# rpi_ad7705.net
KiCad netlist of a schematic drawn in EAGLE
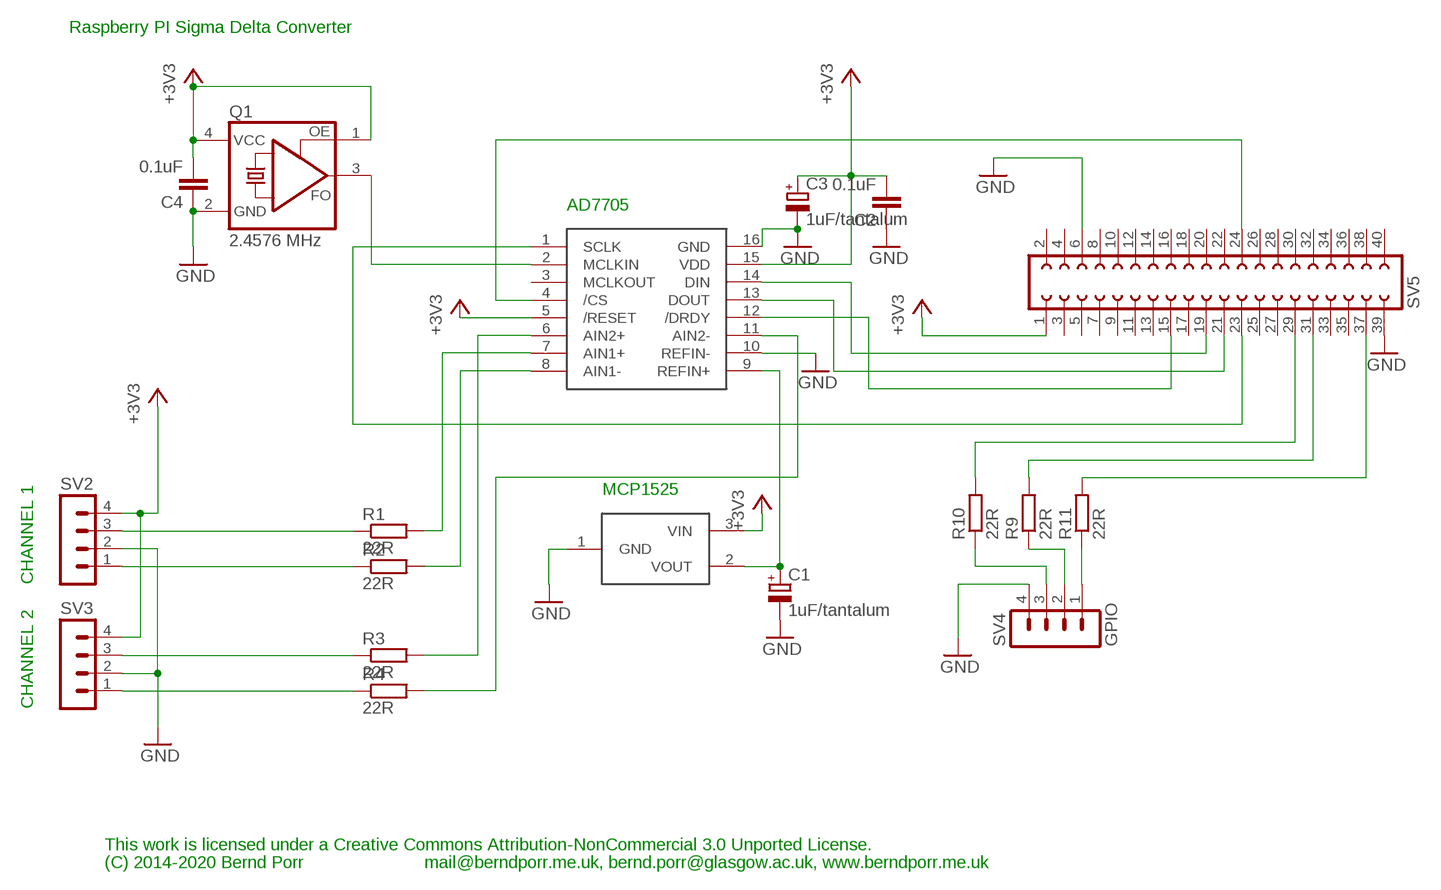
[diagram p0: schematic, sheet 1]

(export (version "E")
  (design (tool "Eeschema 10.0.6"))
  (components
    (comp (ref "C1")
      (value "1uF/tantalum")
      (footprint "eagle-import:TT2D7")
      (libsource (lib "eagle-import") (part "CPOL-EUTT2D7"))
    )
    (comp (ref "C2")
      (value "0.1uF")
      (footprint "eagle-import:C5B2.5")
      (libsource (lib "eagle-import") (part "C5/2.5"))
    )
    (comp (ref "C3")
      (value "1uF/tantalum")
      (footprint "eagle-import:TT2D7")
      (libsource (lib "eagle-import") (part "CPOL-EUTT2D7"))
    )
    (comp (ref "C4")
      (value "0.1uF")
      (footprint "eagle-import:C5B2.5")
      (libsource (lib "eagle-import") (part "C5/2.5"))
    )
    (comp (ref "Q1")
      (value "2.4576 MHz")
      (footprint "eagle-import:ASF")
      (fields (field (name "MPN") "ASFLM1-50.000MHZ-C-T"))
      (libsource (lib "eagle-import") (part "ASFL"))
    )
    (comp (ref "R1")
      (value "22R")
      (footprint "eagle-import:0207_10")
      (libsource (lib "eagle-import") (part "R-EU_0207/10"))
    )
    (comp (ref "R2")
      (value "22R")
      (footprint "eagle-import:0207_10")
      (libsource (lib "eagle-import") (part "R-EU_0207/10"))
    )
    (comp (ref "R3")
      (value "22R")
      (footprint "eagle-import:0207_10")
      (libsource (lib "eagle-import") (part "R-EU_0207/10"))
    )
    (comp (ref "R4")
      (value "22R")
      (footprint "eagle-import:0207_10")
      (libsource (lib "eagle-import") (part "R-EU_0207/10"))
    )
    (comp (ref "R9")
      (value "22R")
      (footprint "eagle-import:0207_10")
      (libsource (lib "eagle-import") (part "R-EU_0207/10"))
    )
    (comp (ref "R10")
      (value "22R")
      (footprint "eagle-import:0207_10")
      (libsource (lib "eagle-import") (part "R-EU_0207/10"))
    )
    (comp (ref "R11")
      (value "22R")
      (footprint "eagle-import:0207_10")
      (libsource (lib "eagle-import") (part "R-EU_0207/10"))
    )
    (comp (ref "SV2")
      (value "MA04-1")
      (footprint "eagle-import:MA04-1")
      (libsource (lib "eagle-import") (part "MA04-1"))
    )
    (comp (ref "SV3")
      (value "MA04-1")
      (footprint "eagle-import:MA04-1")
      (libsource (lib "eagle-import") (part "MA04-1"))
    )
    (comp (ref "SV4")
      (value "GPIO")
      (footprint "eagle-import:MA04-1")
      (libsource (lib "eagle-import") (part "MA04-1"))
    )
    (comp (ref "SV5")
      (value "FE20-2")
      (footprint "eagle-import:FE20-2")
      (libsource (lib "eagle-import") (part "FE20-2"))
    )
    (comp (ref "U$1")
      (value "AD7705")
      (footprint "eagle-import:DIP16")
      (libsource (lib "eagle-import") (part "AD7705"))
    )
    (comp (ref "U$2")
      (value "MCP1525")
      (footprint "eagle-import:TO92")
      (libsource (lib "eagle-import") (part "MCP1525"))
    )
  )
  (nets
    (net (code "1") (name "+3V3") (class "Default")
      (node (ref "C2") (pin "2") (pinfunction "2_2") (pintype "passive"))
      (node (ref "C3") (pin "+") (pinfunction "+_+") (pintype "passive"))
      (node (ref "C4") (pin "2") (pinfunction "2_2") (pintype "passive"))
      (node (ref "Q1") (pin "1") (pinfunction "OE_1") (pintype "input"))
      (node (ref "Q1") (pin "4") (pinfunction "VCC_4") (pintype "power_in"))
      (node (ref "SV2") (pin "4") (pinfunction "4_4") (pintype "passive"))
      (node (ref "SV3") (pin "4") (pinfunction "4_4") (pintype "passive"))
      (node (ref "SV5") (pin "1") (pinfunction "1_1") (pintype "passive"))
      (node (ref "U$1") (pin "15") (pinfunction "VDD_15") (pintype "power_in"))
      (node (ref "U$1") (pin "5") (pinfunction "/RESET_5") (pintype "bidirectional"))
      (node (ref "U$2") (pin "3") (pinfunction "VIN_3") (pintype "power_in"))
    )
    (net (code "2") (name "GND") (class "Default")
      (node (ref "C1") (pin "-") (pinfunction "-_-") (pintype "passive"))
      (node (ref "C2") (pin "1") (pinfunction "1_1") (pintype "passive"))
      (node (ref "C3") (pin "-") (pinfunction "-_-") (pintype "passive"))
      (node (ref "C4") (pin "1") (pinfunction "1_1") (pintype "passive"))
      (node (ref "Q1") (pin "2") (pinfunction "GND_2") (pintype "power_in"))
      (node (ref "SV2") (pin "2") (pinfunction "2_2") (pintype "passive"))
      (node (ref "SV3") (pin "2") (pinfunction "2_2") (pintype "passive"))
      (node (ref "SV4") (pin "4") (pinfunction "4_4") (pintype "passive"))
      (node (ref "SV5") (pin "39") (pinfunction "39_39") (pintype "passive"))
      (node (ref "SV5") (pin "6") (pinfunction "6_6") (pintype "passive"))
      (node (ref "U$1") (pin "10") (pinfunction "REFIN-_10") (pintype "bidirectional"))
      (node (ref "U$1") (pin "16") (pinfunction "GND_16") (pintype "power_in"))
      (node (ref "U$2") (pin "1") (pinfunction "GND_1") (pintype "power_in"))
    )
    (net (code "3") (name "Net-(Q1-FO)") (class "Default")
      (node (ref "Q1") (pin "3") (pinfunction "FO_3") (pintype "output"))
      (node (ref "U$1") (pin "2") (pinfunction "MCLKIN_2") (pintype "bidirectional"))
    )
    (net (code "4") (name "Net-(R1-Pad1)") (class "Default")
      (node (ref "R1") (pin "1") (pinfunction "1_1") (pintype "passive"))
      (node (ref "SV2") (pin "3") (pinfunction "3_3") (pintype "passive"))
    )
    (net (code "5") (name "Net-(R2-Pad1)") (class "Default")
      (node (ref "R2") (pin "1") (pinfunction "1_1") (pintype "passive"))
      (node (ref "SV2") (pin "1") (pinfunction "1_1") (pintype "passive"))
    )
    (net (code "6") (name "Net-(R3-Pad1)") (class "Default")
      (node (ref "R3") (pin "1") (pinfunction "1_1") (pintype "passive"))
      (node (ref "SV3") (pin "3") (pinfunction "3_3") (pintype "passive"))
    )
    (net (code "7") (name "Net-(R4-Pad1)") (class "Default")
      (node (ref "R4") (pin "1") (pinfunction "1_1") (pintype "passive"))
      (node (ref "SV3") (pin "1") (pinfunction "1_1") (pintype "passive"))
    )
    (net (code "8") (name "Net-(R9-Pad1)") (class "Default")
      (node (ref "R9") (pin "1") (pinfunction "1_1") (pintype "passive"))
      (node (ref "SV4") (pin "2") (pinfunction "2_2") (pintype "passive"))
    )
    (net (code "9") (name "Net-(R9-Pad2)") (class "Default")
      (node (ref "R9") (pin "2") (pinfunction "2_2") (pintype "passive"))
      (node (ref "SV5") (pin "31") (pinfunction "31_31") (pintype "passive"))
    )
    (net (code "10") (name "Net-(R10-Pad1)") (class "Default")
      (node (ref "R10") (pin "1") (pinfunction "1_1") (pintype "passive"))
      (node (ref "SV4") (pin "3") (pinfunction "3_3") (pintype "passive"))
    )
    (net (code "11") (name "Net-(R10-Pad2)") (class "Default")
      (node (ref "R10") (pin "2") (pinfunction "2_2") (pintype "passive"))
      (node (ref "SV5") (pin "29") (pinfunction "29_29") (pintype "passive"))
    )
    (net (code "12") (name "Net-(R11-Pad1)") (class "Default")
      (node (ref "R11") (pin "1") (pinfunction "1_1") (pintype "passive"))
      (node (ref "SV4") (pin "1") (pinfunction "1_1") (pintype "passive"))
    )
    (net (code "13") (name "Net-(R11-Pad2)") (class "Default")
      (node (ref "R11") (pin "2") (pinfunction "2_2") (pintype "passive"))
      (node (ref "SV5") (pin "37") (pinfunction "37_37") (pintype "passive"))
    )
    (net (code "14") (name "Net-(U$1-AIN1+)") (class "Default")
      (node (ref "R1") (pin "2") (pinfunction "2_2") (pintype "passive"))
      (node (ref "U$1") (pin "7") (pinfunction "AIN1+_7") (pintype "bidirectional"))
    )
    (net (code "15") (name "Net-(U$1-AIN1-)") (class "Default")
      (node (ref "R2") (pin "2") (pinfunction "2_2") (pintype "passive"))
      (node (ref "U$1") (pin "8") (pinfunction "AIN1-_8") (pintype "bidirectional"))
    )
    (net (code "16") (name "Net-(U$1-AIN2+)") (class "Default")
      (node (ref "R3") (pin "2") (pinfunction "2_2") (pintype "passive"))
      (node (ref "U$1") (pin "6") (pinfunction "AIN2+_6") (pintype "bidirectional"))
    )
    (net (code "17") (name "Net-(U$1-AIN2-)") (class "Default")
      (node (ref "R4") (pin "2") (pinfunction "2_2") (pintype "passive"))
      (node (ref "U$1") (pin "11") (pinfunction "AIN2-_11") (pintype "bidirectional"))
    )
    (net (code "18") (name "Net-(U$1-DIN)") (class "Default")
      (node (ref "SV5") (pin "19") (pinfunction "19_19") (pintype "passive"))
      (node (ref "U$1") (pin "14") (pinfunction "DIN_14") (pintype "bidirectional"))
    )
    (net (code "19") (name "Net-(U$1-DOUT)") (class "Default")
      (node (ref "SV5") (pin "21") (pinfunction "21_21") (pintype "passive"))
      (node (ref "U$1") (pin "13") (pinfunction "DOUT_13") (pintype "bidirectional"))
    )
    (net (code "20") (name "Net-(U$1-REFIN+)") (class "Default")
      (node (ref "C1") (pin "+") (pinfunction "+_+") (pintype "passive"))
      (node (ref "U$1") (pin "9") (pinfunction "REFIN+_9") (pintype "bidirectional"))
      (node (ref "U$2") (pin "2") (pinfunction "VOUT_2") (pintype "power_in"))
    )
    (net (code "21") (name "Net-(U$1-SCLK)") (class "Default")
      (node (ref "SV5") (pin "23") (pinfunction "23_23") (pintype "passive"))
      (node (ref "U$1") (pin "1") (pinfunction "SCLK_1") (pintype "bidirectional"))
    )
    (net (code "22") (name "Net-(U$1-{slash}CS)") (class "Default")
      (node (ref "SV5") (pin "24") (pinfunction "24_24") (pintype "passive"))
      (node (ref "U$1") (pin "4") (pinfunction "/CS_4") (pintype "bidirectional"))
    )
    (net (code "23") (name "Net-(U$1-{slash}DRDY)") (class "Default")
      (node (ref "SV5") (pin "15") (pinfunction "15_15") (pintype "passive"))
      (node (ref "U$1") (pin "12") (pinfunction "/DRDY_12") (pintype "bidirectional"))
    )
    (net (code "24") (name "unconnected-(SV5-Pad2)") (class "Default")
      (node (ref "SV5") (pin "2") (pinfunction "2_2") (pintype "passive"))
    )
    (net (code "25") (name "unconnected-(SV5-Pad3)") (class "Default")
      (node (ref "SV5") (pin "3") (pinfunction "3_3") (pintype "passive"))
    )
    (net (code "26") (name "unconnected-(SV5-Pad4)") (class "Default")
      (node (ref "SV5") (pin "4") (pinfunction "4_4") (pintype "passive"))
    )
    (net (code "27") (name "unconnected-(SV5-Pad5)") (class "Default")
      (node (ref "SV5") (pin "5") (pinfunction "5_5") (pintype "passive"))
    )
    (net (code "28") (name "unconnected-(SV5-Pad7)") (class "Default")
      (node (ref "SV5") (pin "7") (pinfunction "7_7") (pintype "passive"))
    )
    (net (code "29") (name "unconnected-(SV5-Pad8)") (class "Default")
      (node (ref "SV5") (pin "8") (pinfunction "8_8") (pintype "passive"))
    )
    (net (code "30") (name "unconnected-(SV5-Pad9)") (class "Default")
      (node (ref "SV5") (pin "9") (pinfunction "9_9") (pintype "passive"))
    )
    (net (code "31") (name "unconnected-(SV5-Pad10)") (class "Default")
      (node (ref "SV5") (pin "10") (pinfunction "10_10") (pintype "passive"))
    )
    (net (code "32") (name "unconnected-(SV5-Pad11)") (class "Default")
      (node (ref "SV5") (pin "11") (pinfunction "11_11") (pintype "passive"))
    )
    (net (code "33") (name "unconnected-(SV5-Pad12)") (class "Default")
      (node (ref "SV5") (pin "12") (pinfunction "12_12") (pintype "passive"))
    )
    (net (code "34") (name "unconnected-(SV5-Pad13)") (class "Default")
      (node (ref "SV5") (pin "13") (pinfunction "13_13") (pintype "passive"))
    )
    (net (code "35") (name "unconnected-(SV5-Pad14)") (class "Default")
      (node (ref "SV5") (pin "14") (pinfunction "14_14") (pintype "passive"))
    )
    (net (code "36") (name "unconnected-(SV5-Pad16)") (class "Default")
      (node (ref "SV5") (pin "16") (pinfunction "16_16") (pintype "passive"))
    )
    (net (code "37") (name "unconnected-(SV5-Pad17)") (class "Default")
      (node (ref "SV5") (pin "17") (pinfunction "17_17") (pintype "passive"))
    )
    (net (code "38") (name "unconnected-(SV5-Pad18)") (class "Default")
      (node (ref "SV5") (pin "18") (pinfunction "18_18") (pintype "passive"))
    )
    (net (code "39") (name "unconnected-(SV5-Pad20)") (class "Default")
      (node (ref "SV5") (pin "20") (pinfunction "20_20") (pintype "passive"))
    )
    (net (code "40") (name "unconnected-(SV5-Pad22)") (class "Default")
      (node (ref "SV5") (pin "22") (pinfunction "22_22") (pintype "passive"))
    )
    (net (code "41") (name "unconnected-(SV5-Pad25)") (class "Default")
      (node (ref "SV5") (pin "25") (pinfunction "25_25") (pintype "passive"))
    )
    (net (code "42") (name "unconnected-(SV5-Pad26)") (class "Default")
      (node (ref "SV5") (pin "26") (pinfunction "26_26") (pintype "passive"))
    )
    (net (code "43") (name "unconnected-(SV5-Pad27)") (class "Default")
      (node (ref "SV5") (pin "27") (pinfunction "27_27") (pintype "passive"))
    )
    (net (code "44") (name "unconnected-(SV5-Pad28)") (class "Default")
      (node (ref "SV5") (pin "28") (pinfunction "28_28") (pintype "passive"))
    )
    (net (code "45") (name "unconnected-(SV5-Pad30)") (class "Default")
      (node (ref "SV5") (pin "30") (pinfunction "30_30") (pintype "passive"))
    )
    (net (code "46") (name "unconnected-(SV5-Pad32)") (class "Default")
      (node (ref "SV5") (pin "32") (pinfunction "32_32") (pintype "passive"))
    )
    (net (code "47") (name "unconnected-(SV5-Pad33)") (class "Default")
      (node (ref "SV5") (pin "33") (pinfunction "33_33") (pintype "passive"))
    )
    (net (code "48") (name "unconnected-(SV5-Pad34)") (class "Default")
      (node (ref "SV5") (pin "34") (pinfunction "34_34") (pintype "passive"))
    )
    (net (code "49") (name "unconnected-(SV5-Pad35)") (class "Default")
      (node (ref "SV5") (pin "35") (pinfunction "35_35") (pintype "passive"))
    )
    (net (code "50") (name "unconnected-(SV5-Pad36)") (class "Default")
      (node (ref "SV5") (pin "36") (pinfunction "36_36") (pintype "passive"))
    )
    (net (code "51") (name "unconnected-(SV5-Pad38)") (class "Default")
      (node (ref "SV5") (pin "38") (pinfunction "38_38") (pintype "passive"))
    )
    (net (code "52") (name "unconnected-(SV5-Pad40)") (class "Default")
      (node (ref "SV5") (pin "40") (pinfunction "40_40") (pintype "passive"))
    )
    (net (code "53") (name "unconnected-(U$1-MCLKOUT-Pad3)") (class "Default")
      (node (ref "U$1") (pin "3") (pinfunction "MCLKOUT_3") (pintype "bidirectional"))
    )
  )
)
